# RF_Power_Meter.net
KiCad netlist of a schematic drawn in EAGLE
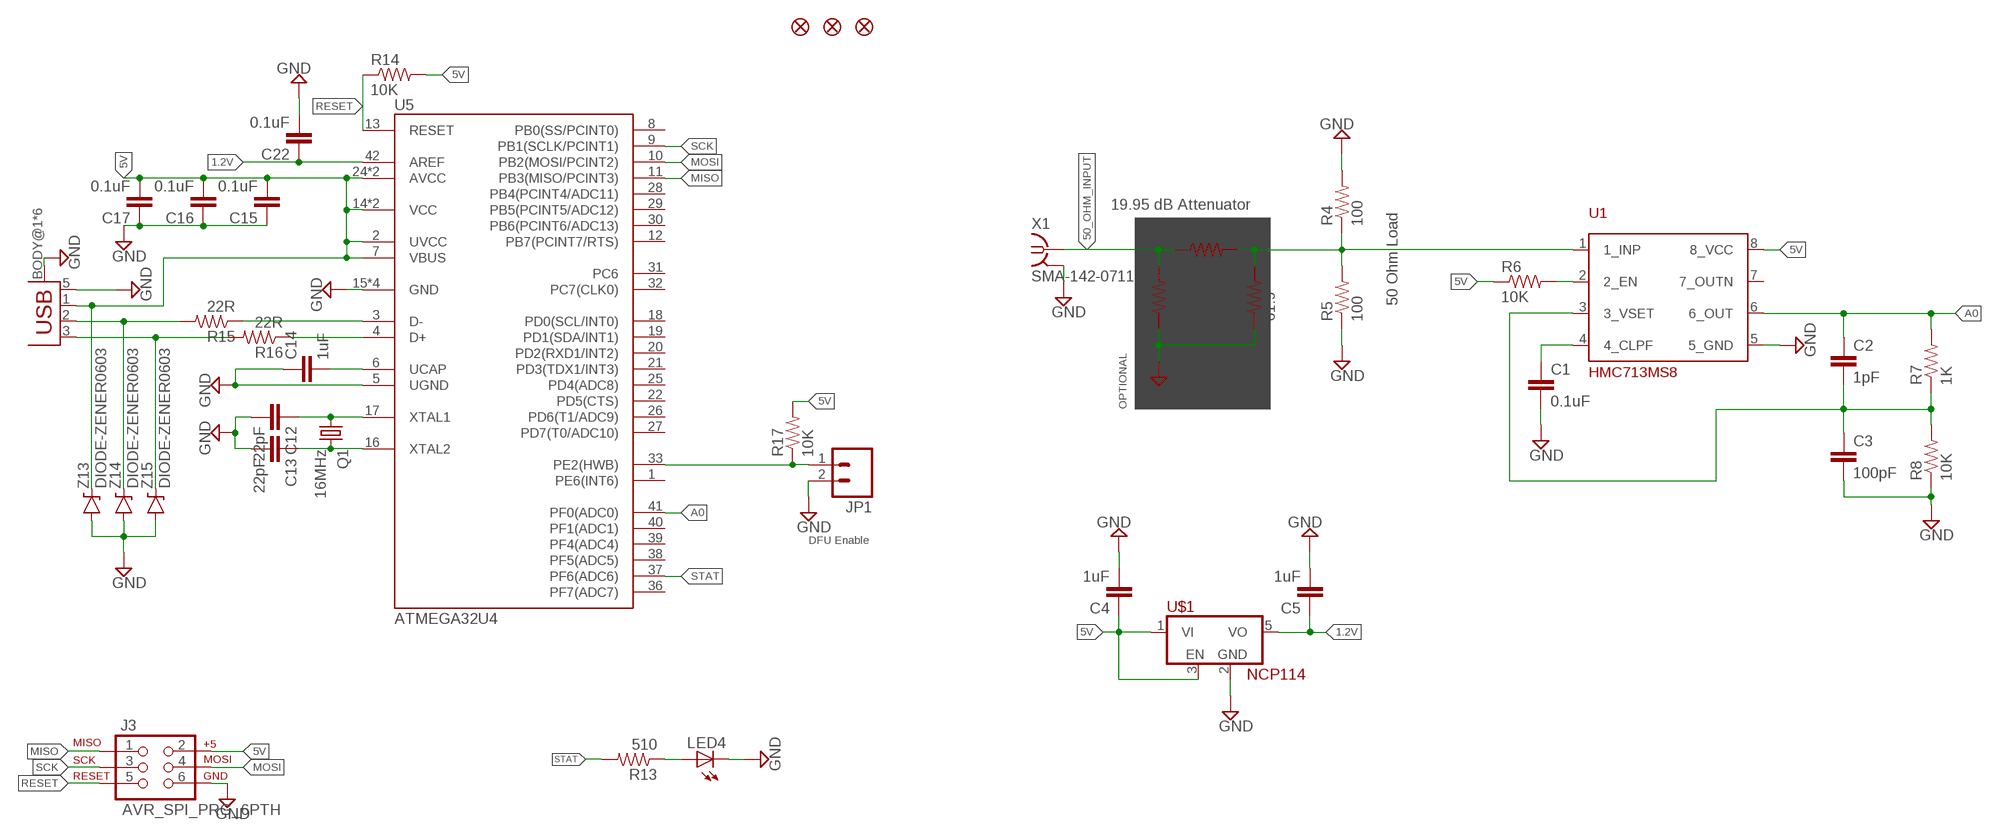
[diagram p0: schematic, sheet 1]

(export (version "E")
  (design (tool "Eeschema 10.0.6"))
  (components
    (comp (ref "C1")
      (value "0.1uF")
      (footprint "eagle-import:0603-CAP")
      (libsource (lib "eagle-import") (part "CAP0603-CAP"))
    )
    (comp (ref "C2")
      (value "1pF")
      (footprint "eagle-import:0603-CAP")
      (libsource (lib "eagle-import") (part "CAP0603-CAP"))
    )
    (comp (ref "C3")
      (value "100pF")
      (footprint "eagle-import:0603-CAP")
      (libsource (lib "eagle-import") (part "CAP0603-CAP"))
    )
    (comp (ref "C4")
      (value "1uF")
      (footprint "eagle-import:0603-CAP")
      (libsource (lib "eagle-import") (part "CAP0603-CAP"))
    )
    (comp (ref "C5")
      (value "1uF")
      (footprint "eagle-import:0603-CAP")
      (libsource (lib "eagle-import") (part "CAP0603-CAP"))
    )
    (comp (ref "C12")
      (value "22pF")
      (footprint "eagle-import:0603-CAP")
      (libsource (lib "eagle-import") (part "CAP0603-CAP"))
    )
    (comp (ref "C13")
      (value "22pF")
      (footprint "eagle-import:0603-CAP")
      (libsource (lib "eagle-import") (part "CAP0603-CAP"))
    )
    (comp (ref "C14")
      (value "1uF")
      (footprint "eagle-import:0603-CAP")
      (libsource (lib "eagle-import") (part "CAP0603-CAP"))
    )
    (comp (ref "C15")
      (value "0.1uF")
      (footprint "eagle-import:0603-CAP")
      (libsource (lib "eagle-import") (part "CAP0603-CAP"))
    )
    (comp (ref "C16")
      (value "0.1uF")
      (footprint "eagle-import:0603-CAP")
      (libsource (lib "eagle-import") (part "CAP0603-CAP"))
    )
    (comp (ref "C17")
      (value "0.1uF")
      (footprint "eagle-import:0603-CAP")
      (libsource (lib "eagle-import") (part "CAP0603-CAP"))
    )
    (comp (ref "C22")
      (value "0.1uF")
      (footprint "eagle-import:0603-CAP")
      (libsource (lib "eagle-import") (part "CAP0603-CAP"))
    )
    (comp (ref "J3")
      (value "AVR_SPI_PRG_6PTH")
      (footprint "eagle-import:2X3")
      (libsource (lib "eagle-import") (part "AVR_SPI_PRG_6PTH"))
    )
    (comp (ref "JP1")
      (value "M02PTH3")
      (footprint "eagle-import:1X02_LONGPADS")
      (libsource (lib "eagle-import") (part "M02PTH3"))
    )
    (comp (ref "JP2")
      (value "FIDUCIAL1X2")
      (footprint "eagle-import:FIDUCIAL-1X2")
      (libsource (lib "eagle-import") (part "FIDUCIAL1X2"))
    )
    (comp (ref "JP3")
      (value "FIDUCIAL1X2")
      (footprint "eagle-import:FIDUCIAL-1X2")
      (libsource (lib "eagle-import") (part "FIDUCIAL1X2"))
    )
    (comp (ref "JP4")
      (value "FIDUCIAL1X2")
      (footprint "eagle-import:FIDUCIAL-1X2")
      (libsource (lib "eagle-import") (part "FIDUCIAL1X2"))
    )
    (comp (ref "LED4")
      (value "LED0603")
      (footprint "eagle-import:LED-0603")
      (libsource (lib "eagle-import") (part "LED0603"))
    )
    (comp (ref "Q1")
      (value "16MHz")
      (footprint "eagle-import:CRYSTAL_3.2X2.5")
      (libsource (lib "eagle-import") (part "CRYSTAL3.2X2.5"))
    )
    (comp (ref "R1")
      (value "61.9")
      (footprint "eagle-import:1206")
      (libsource (lib "eagle-import") (part "RESISTOR1206"))
    )
    (comp (ref "R2")
      (value "249")
      (footprint "eagle-import:1206")
      (libsource (lib "eagle-import") (part "RESISTOR1206"))
    )
    (comp (ref "R3")
      (value "61.9")
      (footprint "eagle-import:1206")
      (libsource (lib "eagle-import") (part "RESISTOR1206"))
    )
    (comp (ref "R4")
      (value "100")
      (footprint "eagle-import:1206")
      (libsource (lib "eagle-import") (part "RESISTOR1206"))
    )
    (comp (ref "R5")
      (value "100")
      (footprint "eagle-import:1206")
      (libsource (lib "eagle-import") (part "RESISTOR1206"))
    )
    (comp (ref "R6")
      (value "10K")
      (footprint "eagle-import:0603-RES")
      (libsource (lib "eagle-import") (part "RESISTOR0603-RES"))
    )
    (comp (ref "R7")
      (value "1K")
      (footprint "eagle-import:0603-RES")
      (libsource (lib "eagle-import") (part "RESISTOR0603-RES"))
    )
    (comp (ref "R8")
      (value "10K")
      (footprint "eagle-import:0603-RES")
      (libsource (lib "eagle-import") (part "RESISTOR0603-RES"))
    )
    (comp (ref "R13")
      (value "510")
      (footprint "eagle-import:0603-RES")
      (libsource (lib "eagle-import") (part "RESISTOR0603-RES"))
    )
    (comp (ref "R14")
      (value "10K")
      (footprint "eagle-import:0603-RES")
      (libsource (lib "eagle-import") (part "RESISTOR0603-RES"))
    )
    (comp (ref "R15")
      (value "22R")
      (footprint "eagle-import:0603-RES")
      (libsource (lib "eagle-import") (part "RESISTOR0603-RES"))
    )
    (comp (ref "R16")
      (value "22R")
      (footprint "eagle-import:0603-RES")
      (libsource (lib "eagle-import") (part "RESISTOR0603-RES"))
    )
    (comp (ref "R17")
      (value "10K")
      (footprint "eagle-import:0603-RES")
      (libsource (lib "eagle-import") (part "RESISTOR0603-RES"))
    )
    (comp (ref "U$1")
      (value "NCP114")
      (footprint "eagle-import:SOT-23-5")
      (libsource (lib "eagle-import") (part "NCP114"))
    )
    (comp (ref "U1")
      (value "HMC713MS8")
      (footprint "eagle-import:MSOP-8")
      (libsource (lib "eagle-import") (part "HMC713MS8"))
    )
    (comp (ref "U5")
      (value "ATMEGA32U4")
      (footprint "eagle-import:TQFP-44")
      (libsource (lib "eagle-import") (part "ATMEGA32U4"))
    )
    (comp (ref "X1")
      (value "SMA-142-0711-821/826")
      (footprint "eagle-import:J502-ND-142-0711-821_826")
      (fields (field (name "MF") "JOHNSON COMPONENTS") (field (name "MPN") "142-0711-821"))
      (libsource (lib "eagle-import") (part "SMA-142-0711-821/826"))
    )
    (comp (ref "X3")
      (value "USB-MICROB")
      (footprint "eagle-import:USB-MICROB-10118192")
      (libsource (lib "eagle-import") (part "USB-MICROB"))
    )
    (comp (ref "Z13")
      (value "DIODE-ZENER0603")
      (footprint "eagle-import:0603-DIODE")
      (libsource (lib "eagle-import") (part "DIODE-ZENER0603"))
    )
    (comp (ref "Z14")
      (value "DIODE-ZENER0603")
      (footprint "eagle-import:0603-DIODE")
      (libsource (lib "eagle-import") (part "DIODE-ZENER0603"))
    )
    (comp (ref "Z15")
      (value "DIODE-ZENER0603")
      (footprint "eagle-import:0603-DIODE")
      (libsource (lib "eagle-import") (part "DIODE-ZENER0603"))
    )
  )
  (nets
    (net (code "1") (name "1.2V") (class "Default")
      (node (ref "C22") (pin "1") (pinfunction "1_1") (pintype "passive"))
      (node (ref "C5") (pin "1") (pinfunction "1_1") (pintype "passive"))
      (node (ref "U$1") (pin "5") (pinfunction "VO_5") (pintype "power_in"))
      (node (ref "U5") (pin "42") (pinfunction "AREF_42") (pintype "bidirectional"))
    )
    (net (code "2") (name "5V") (class "Default")
      (node (ref "C15") (pin "2") (pinfunction "2_2") (pintype "passive"))
      (node (ref "C16") (pin "2") (pinfunction "2_2") (pintype "passive"))
      (node (ref "C17") (pin "2") (pinfunction "2_2") (pintype "passive"))
      (node (ref "C4") (pin "1") (pinfunction "1_1") (pintype "passive"))
      (node (ref "J3") (pin "2") (pinfunction "2_2") (pintype "passive"))
      (node (ref "R14") (pin "2") (pinfunction "2_2") (pintype "passive"))
      (node (ref "R17") (pin "2") (pinfunction "2_2") (pintype "passive"))
      (node (ref "R6") (pin "1") (pinfunction "1_1") (pintype "passive"))
      (node (ref "U$1") (pin "1") (pinfunction "VI_1") (pintype "power_in"))
      (node (ref "U$1") (pin "3") (pinfunction "EN_3") (pintype "power_in"))
      (node (ref "U1") (pin "8") (pinfunction "8_VCC_8") (pintype "bidirectional"))
      (node (ref "U5") (pin "14") (pinfunction "VCC_14") (pintype "bidirectional"))
      (node (ref "U5") (pin "2") (pinfunction "UVCC_2") (pintype "bidirectional"))
      (node (ref "U5") (pin "24") (pinfunction "AVCC_24") (pintype "bidirectional"))
      (node (ref "U5") (pin "34") (pinfunction "VCC_34") (pintype "bidirectional"))
      (node (ref "U5") (pin "44") (pinfunction "AVCC_44") (pintype "bidirectional"))
      (node (ref "U5") (pin "7") (pinfunction "VBUS_7") (pintype "bidirectional"))
      (node (ref "X3") (pin "1") (pinfunction "VBUS_1") (pintype "bidirectional"))
      (node (ref "Z13") (pin "C") (pinfunction "C_C") (pintype "passive"))
    )
    (net (code "3") (name "50_OHM_INPUT") (class "Default")
      (node (ref "R1") (pin "2") (pinfunction "2_2") (pintype "passive"))
      (node (ref "R2") (pin "1") (pinfunction "1_1") (pintype "passive"))
      (node (ref "X1") (pin "1") (pinfunction "1_1") (pintype "passive"))
    )
    (net (code "4") (name "A0") (class "Default")
      (node (ref "C2") (pin "1") (pinfunction "1_1") (pintype "passive"))
      (node (ref "R7") (pin "2") (pinfunction "2_2") (pintype "passive"))
      (node (ref "U1") (pin "6") (pinfunction "6_OUT_6") (pintype "bidirectional"))
      (node (ref "U5") (pin "41") (pinfunction "PF0(ADC0)_41") (pintype "bidirectional"))
    )
    (net (code "5") (name "GND") (class "Default")
      (node (ref "C1") (pin "2") (pinfunction "2_2") (pintype "passive"))
      (node (ref "C12") (pin "2") (pinfunction "2_2") (pintype "passive"))
      (node (ref "C13") (pin "2") (pinfunction "2_2") (pintype "passive"))
      (node (ref "C14") (pin "1") (pinfunction "1_1") (pintype "passive"))
      (node (ref "C15") (pin "1") (pinfunction "1_1") (pintype "passive"))
      (node (ref "C16") (pin "1") (pinfunction "1_1") (pintype "passive"))
      (node (ref "C17") (pin "1") (pinfunction "1_1") (pintype "passive"))
      (node (ref "C22") (pin "2") (pinfunction "2_2") (pintype "passive"))
      (node (ref "C3") (pin "2") (pinfunction "2_2") (pintype "passive"))
      (node (ref "C4") (pin "2") (pinfunction "2_2") (pintype "passive"))
      (node (ref "C5") (pin "2") (pinfunction "2_2") (pintype "passive"))
      (node (ref "J3") (pin "6") (pinfunction "6_6") (pintype "passive"))
      (node (ref "JP1") (pin "2") (pinfunction "2_2") (pintype "passive"))
      (node (ref "LED4") (pin "C") (pinfunction "C_C") (pintype "passive"))
      (node (ref "R1") (pin "1") (pinfunction "1_1") (pintype "passive"))
      (node (ref "R3") (pin "1") (pinfunction "1_1") (pintype "passive"))
      (node (ref "R4") (pin "2") (pinfunction "2_2") (pintype "passive"))
      (node (ref "R5") (pin "1") (pinfunction "1_1") (pintype "passive"))
      (node (ref "R8") (pin "1") (pinfunction "1_1") (pintype "passive"))
      (node (ref "U$1") (pin "2") (pinfunction "GND_2") (pintype "power_in"))
      (node (ref "U1") (pin "5") (pinfunction "5_GND_5") (pintype "bidirectional"))
      (node (ref "U5") (pin "15") (pinfunction "GND_15") (pintype "bidirectional"))
      (node (ref "U5") (pin "23") (pinfunction "GND_23") (pintype "bidirectional"))
      (node (ref "U5") (pin "35") (pinfunction "GND_35") (pintype "bidirectional"))
      (node (ref "U5") (pin "43") (pinfunction "GND_43") (pintype "bidirectional"))
      (node (ref "U5") (pin "5") (pinfunction "UGND_5") (pintype "bidirectional"))
      (node (ref "X1") (pin "G@1") (pinfunction "2_G@1") (pintype "passive"))
      (node (ref "X1") (pin "G@2") (pinfunction "2_G@2") (pintype "passive"))
      (node (ref "X1") (pin "G@3") (pinfunction "2_G@3") (pintype "passive"))
      (node (ref "X1") (pin "G@4") (pinfunction "2_G@4") (pintype "passive"))
      (node (ref "X3") (pin "5") (pinfunction "GND_5") (pintype "bidirectional"))
      (node (ref "X3") (pin "BODY@1") (pinfunction "BODY_BODY@1") (pintype "bidirectional"))
      (node (ref "X3") (pin "BODY@2") (pinfunction "BODY_BODY@2") (pintype "bidirectional"))
      (node (ref "X3") (pin "BODY@3") (pinfunction "BODY_BODY@3") (pintype "bidirectional"))
      (node (ref "X3") (pin "BODY@4") (pinfunction "BODY_BODY@4") (pintype "bidirectional"))
      (node (ref "X3") (pin "BODY@5") (pinfunction "BODY_BODY@5") (pintype "bidirectional"))
      (node (ref "X3") (pin "BODY@6") (pinfunction "BODY_BODY@6") (pintype "bidirectional"))
      (node (ref "Z13") (pin "A") (pinfunction "A_A") (pintype "passive"))
      (node (ref "Z14") (pin "A") (pinfunction "A_A") (pintype "passive"))
      (node (ref "Z15") (pin "A") (pinfunction "A_A") (pintype "passive"))
    )
    (net (code "6") (name "MISO") (class "Default")
      (node (ref "J3") (pin "1") (pinfunction "1_1") (pintype "passive"))
      (node (ref "U5") (pin "11") (pinfunction "PB3(MISO/PCINT3)_11") (pintype "bidirectional"))
    )
    (net (code "7") (name "MOSI") (class "Default")
      (node (ref "J3") (pin "4") (pinfunction "4_4") (pintype "passive"))
      (node (ref "U5") (pin "10") (pinfunction "PB2(MOSI/PCINT2)_10") (pintype "bidirectional"))
    )
    (net (code "8") (name "Net-(LED4-PadA)") (class "Default")
      (node (ref "LED4") (pin "A") (pinfunction "A_A") (pintype "passive"))
      (node (ref "R13") (pin "1") (pinfunction "1_1") (pintype "passive"))
    )
    (net (code "9") (name "Net-(Q1-1)") (class "Default")
      (node (ref "C12") (pin "1") (pinfunction "1_1") (pintype "passive"))
      (node (ref "Q1") (pin "P$1") (pinfunction "1_P$1") (pintype "passive"))
      (node (ref "U5") (pin "17") (pinfunction "XTAL1_17") (pintype "bidirectional"))
    )
    (net (code "10") (name "Net-(Q1-2)") (class "Default")
      (node (ref "C13") (pin "1") (pinfunction "1_1") (pintype "passive"))
      (node (ref "Q1") (pin "P$3") (pinfunction "2_P$3") (pintype "passive"))
      (node (ref "U5") (pin "16") (pinfunction "XTAL2_16") (pintype "bidirectional"))
    )
    (net (code "11") (name "Net-(U1-1_INP)") (class "Default")
      (node (ref "R2") (pin "2") (pinfunction "2_2") (pintype "passive"))
      (node (ref "R3") (pin "2") (pinfunction "2_2") (pintype "passive"))
      (node (ref "R4") (pin "1") (pinfunction "1_1") (pintype "passive"))
      (node (ref "R5") (pin "2") (pinfunction "2_2") (pintype "passive"))
      (node (ref "U1") (pin "1") (pinfunction "1_INP_1") (pintype "bidirectional"))
    )
    (net (code "12") (name "Net-(U1-2_EN)") (class "Default")
      (node (ref "R6") (pin "2") (pinfunction "2_2") (pintype "passive"))
      (node (ref "U1") (pin "2") (pinfunction "2_EN_2") (pintype "bidirectional"))
    )
    (net (code "13") (name "Net-(U1-3_VSET)") (class "Default")
      (node (ref "C2") (pin "2") (pinfunction "2_2") (pintype "passive"))
      (node (ref "C3") (pin "1") (pinfunction "1_1") (pintype "passive"))
      (node (ref "R7") (pin "1") (pinfunction "1_1") (pintype "passive"))
      (node (ref "R8") (pin "2") (pinfunction "2_2") (pintype "passive"))
      (node (ref "U1") (pin "3") (pinfunction "3_VSET_3") (pintype "bidirectional"))
    )
    (net (code "14") (name "Net-(U1-4_CLPF)") (class "Default")
      (node (ref "C1") (pin "1") (pinfunction "1_1") (pintype "passive"))
      (node (ref "U1") (pin "4") (pinfunction "4_CLPF_4") (pintype "bidirectional"))
    )
    (net (code "15") (name "Net-(U5-D+)") (class "Default")
      (node (ref "R16") (pin "1") (pinfunction "1_1") (pintype "passive"))
      (node (ref "U5") (pin "4") (pinfunction "D+_4") (pintype "bidirectional"))
    )
    (net (code "16") (name "Net-(U5-D-)") (class "Default")
      (node (ref "R15") (pin "1") (pinfunction "1_1") (pintype "passive"))
      (node (ref "U5") (pin "3") (pinfunction "D-_3") (pintype "bidirectional"))
    )
    (net (code "17") (name "Net-(U5-PE2(HWB))") (class "Default")
      (node (ref "JP1") (pin "1") (pinfunction "1_1") (pintype "passive"))
      (node (ref "R17") (pin "1") (pinfunction "1_1") (pintype "passive"))
      (node (ref "U5") (pin "33") (pinfunction "PE2(HWB)_33") (pintype "bidirectional"))
    )
    (net (code "18") (name "Net-(U5-UCAP)") (class "Default")
      (node (ref "C14") (pin "2") (pinfunction "2_2") (pintype "passive"))
      (node (ref "U5") (pin "6") (pinfunction "UCAP_6") (pintype "bidirectional"))
    )
    (net (code "19") (name "Net-(X3-D+)") (class "Default")
      (node (ref "R16") (pin "2") (pinfunction "2_2") (pintype "passive"))
      (node (ref "X3") (pin "3") (pinfunction "D+_3") (pintype "bidirectional"))
      (node (ref "Z15") (pin "C") (pinfunction "C_C") (pintype "passive"))
    )
    (net (code "20") (name "Net-(X3-D-)") (class "Default")
      (node (ref "R15") (pin "2") (pinfunction "2_2") (pintype "passive"))
      (node (ref "X3") (pin "2") (pinfunction "D-_2") (pintype "bidirectional"))
      (node (ref "Z14") (pin "C") (pinfunction "C_C") (pintype "passive"))
    )
    (net (code "21") (name "RESET") (class "Default")
      (node (ref "J3") (pin "5") (pinfunction "5_5") (pintype "passive"))
      (node (ref "R14") (pin "1") (pinfunction "1_1") (pintype "passive"))
      (node (ref "U5") (pin "13") (pinfunction "RESET_13") (pintype "bidirectional"))
    )
    (net (code "22") (name "SCK") (class "Default")
      (node (ref "J3") (pin "3") (pinfunction "3_3") (pintype "passive"))
      (node (ref "U5") (pin "9") (pinfunction "PB1(SCLK/PCINT1)_9") (pintype "bidirectional"))
    )
    (net (code "23") (name "STAT") (class "Default")
      (node (ref "R13") (pin "2") (pinfunction "2_2") (pintype "passive"))
      (node (ref "U5") (pin "37") (pinfunction "PF6(ADC6)_37") (pintype "bidirectional"))
    )
    (net (code "24") (name "unconnected-(U1-7_OUTN-Pad7)") (class "Default")
      (node (ref "U1") (pin "7") (pinfunction "7_OUTN_7") (pintype "bidirectional"))
    )
    (net (code "25") (name "unconnected-(U5-PB0(SS{slash}PCINT0)-Pad8)") (class "Default")
      (node (ref "U5") (pin "8") (pinfunction "PB0(SS/PCINT0)_8") (pintype "bidirectional"))
    )
    (net (code "26") (name "unconnected-(U5-PB4(PCINT4{slash}ADC11)-Pad28)") (class "Default")
      (node (ref "U5") (pin "28") (pinfunction "PB4(PCINT4/ADC11)_28") (pintype "bidirectional"))
    )
    (net (code "27") (name "unconnected-(U5-PB5(PCINT5{slash}ADC12)-Pad29)") (class "Default")
      (node (ref "U5") (pin "29") (pinfunction "PB5(PCINT5/ADC12)_29") (pintype "bidirectional"))
    )
    (net (code "28") (name "unconnected-(U5-PB6(PCINT6{slash}ADC13)-Pad30)") (class "Default")
      (node (ref "U5") (pin "30") (pinfunction "PB6(PCINT6/ADC13)_30") (pintype "bidirectional"))
    )
    (net (code "29") (name "unconnected-(U5-PB7(PCINT7{slash}RTS)-Pad12)") (class "Default")
      (node (ref "U5") (pin "12") (pinfunction "PB7(PCINT7/RTS)_12") (pintype "bidirectional"))
    )
    (net (code "30") (name "unconnected-(U5-PC6-Pad31)") (class "Default")
      (node (ref "U5") (pin "31") (pinfunction "PC6_31") (pintype "bidirectional"))
    )
    (net (code "31") (name "unconnected-(U5-PC7(CLK0)-Pad32)") (class "Default")
      (node (ref "U5") (pin "32") (pinfunction "PC7(CLK0)_32") (pintype "bidirectional"))
    )
    (net (code "32") (name "unconnected-(U5-PD0(SCL{slash}INT0)-Pad18)") (class "Default")
      (node (ref "U5") (pin "18") (pinfunction "PD0(SCL/INT0)_18") (pintype "bidirectional"))
    )
    (net (code "33") (name "unconnected-(U5-PD1(SDA{slash}INT1)-Pad19)") (class "Default")
      (node (ref "U5") (pin "19") (pinfunction "PD1(SDA/INT1)_19") (pintype "bidirectional"))
    )
    (net (code "34") (name "unconnected-(U5-PD2(RXD1{slash}INT2)-Pad20)") (class "Default")
      (node (ref "U5") (pin "20") (pinfunction "PD2(RXD1/INT2)_20") (pintype "bidirectional"))
    )
    (net (code "35") (name "unconnected-(U5-PD3(TDX1{slash}INT3)-Pad21)") (class "Default")
      (node (ref "U5") (pin "21") (pinfunction "PD3(TDX1/INT3)_21") (pintype "bidirectional"))
    )
    (net (code "36") (name "unconnected-(U5-PD4(ADC8)-Pad25)") (class "Default")
      (node (ref "U5") (pin "25") (pinfunction "PD4(ADC8)_25") (pintype "bidirectional"))
    )
    (net (code "37") (name "unconnected-(U5-PD5(CTS)-Pad22)") (class "Default")
      (node (ref "U5") (pin "22") (pinfunction "PD5(CTS)_22") (pintype "bidirectional"))
    )
    (net (code "38") (name "unconnected-(U5-PD6(T1{slash}ADC9)-Pad26)") (class "Default")
      (node (ref "U5") (pin "26") (pinfunction "PD6(T1/ADC9)_26") (pintype "bidirectional"))
    )
    (net (code "39") (name "unconnected-(U5-PD7(T0{slash}ADC10)-Pad27)") (class "Default")
      (node (ref "U5") (pin "27") (pinfunction "PD7(T0/ADC10)_27") (pintype "bidirectional"))
    )
    (net (code "40") (name "unconnected-(U5-PE6(INT6)-Pad1)") (class "Default")
      (node (ref "U5") (pin "1") (pinfunction "PE6(INT6)_1") (pintype "bidirectional"))
    )
    (net (code "41") (name "unconnected-(U5-PF1(ADC1)-Pad40)") (class "Default")
      (node (ref "U5") (pin "40") (pinfunction "PF1(ADC1)_40") (pintype "bidirectional"))
    )
    (net (code "42") (name "unconnected-(U5-PF4(ADC4)-Pad39)") (class "Default")
      (node (ref "U5") (pin "39") (pinfunction "PF4(ADC4)_39") (pintype "bidirectional"))
    )
    (net (code "43") (name "unconnected-(U5-PF5(ADC5)-Pad38)") (class "Default")
      (node (ref "U5") (pin "38") (pinfunction "PF5(ADC5)_38") (pintype "bidirectional"))
    )
    (net (code "44") (name "unconnected-(U5-PF7(ADC7)-Pad36)") (class "Default")
      (node (ref "U5") (pin "36") (pinfunction "PF7(ADC7)_36") (pintype "bidirectional"))
    )
  )
)
